# BQ25895_BMS_Module.net
KiCad netlist of a schematic drawn in Altium Designer
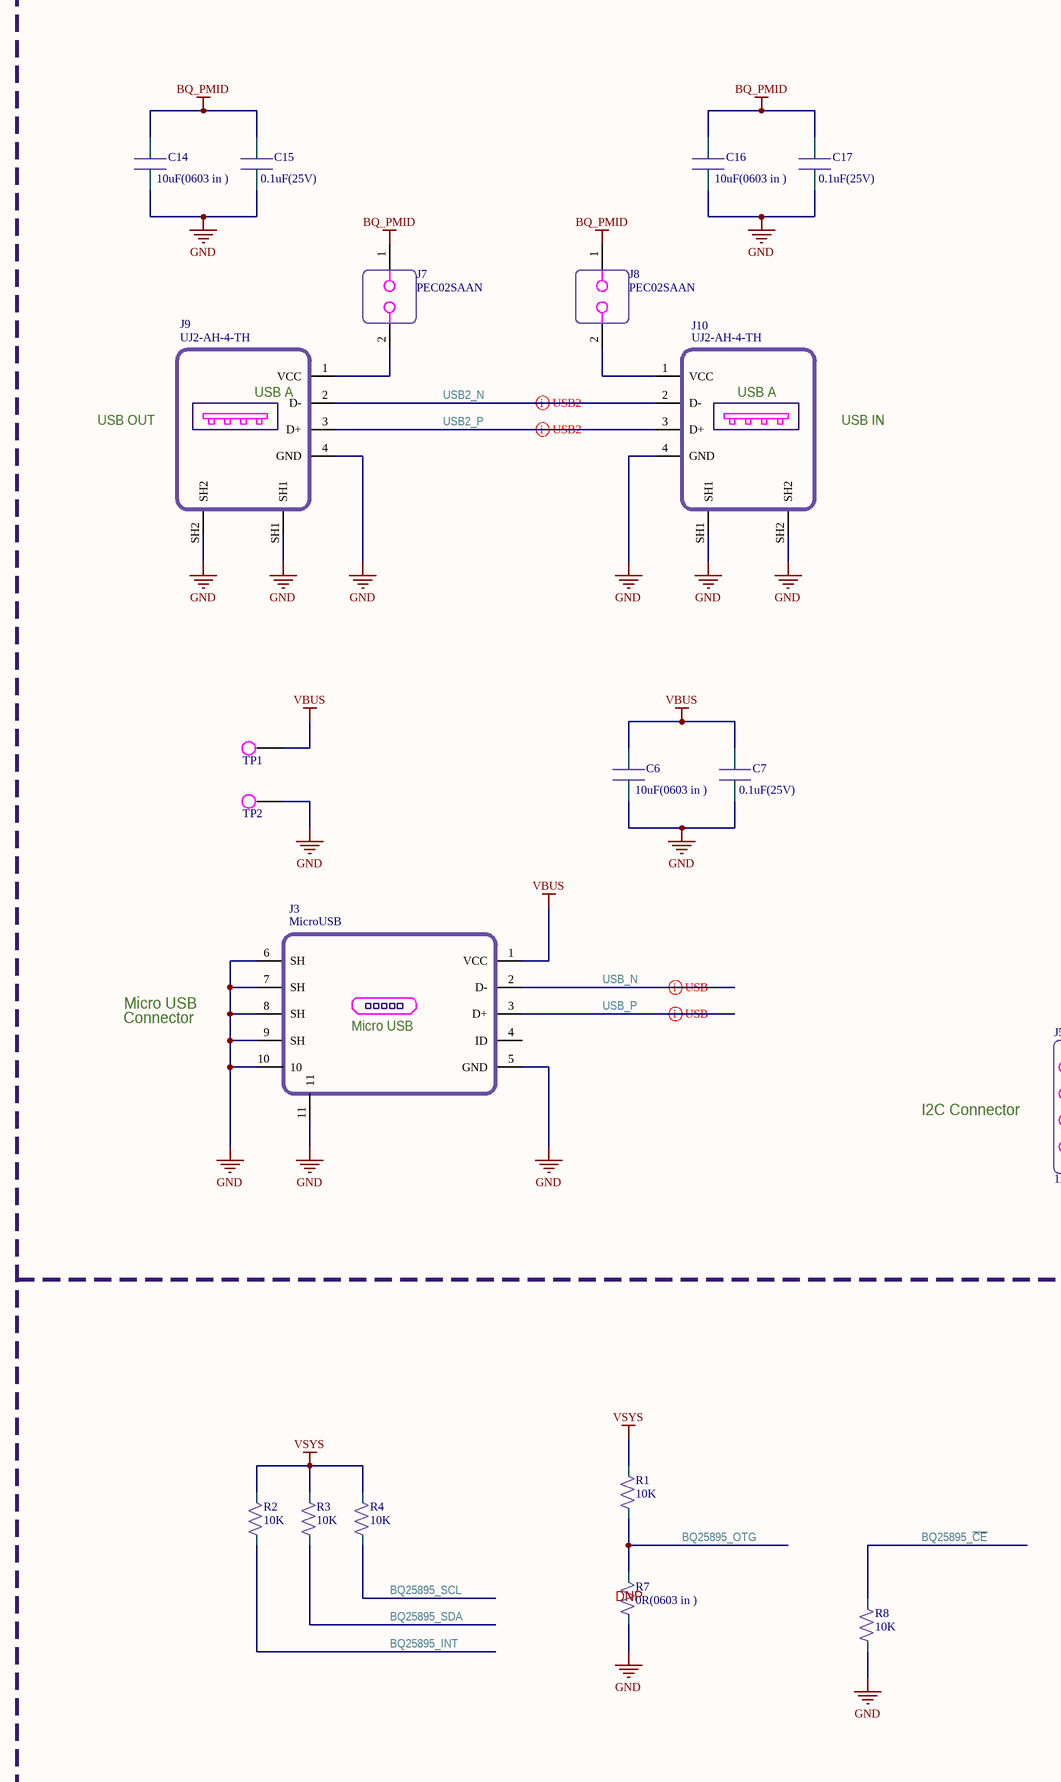
[diagram p0: BQ25895_BMS_Module.SchDoc, left]
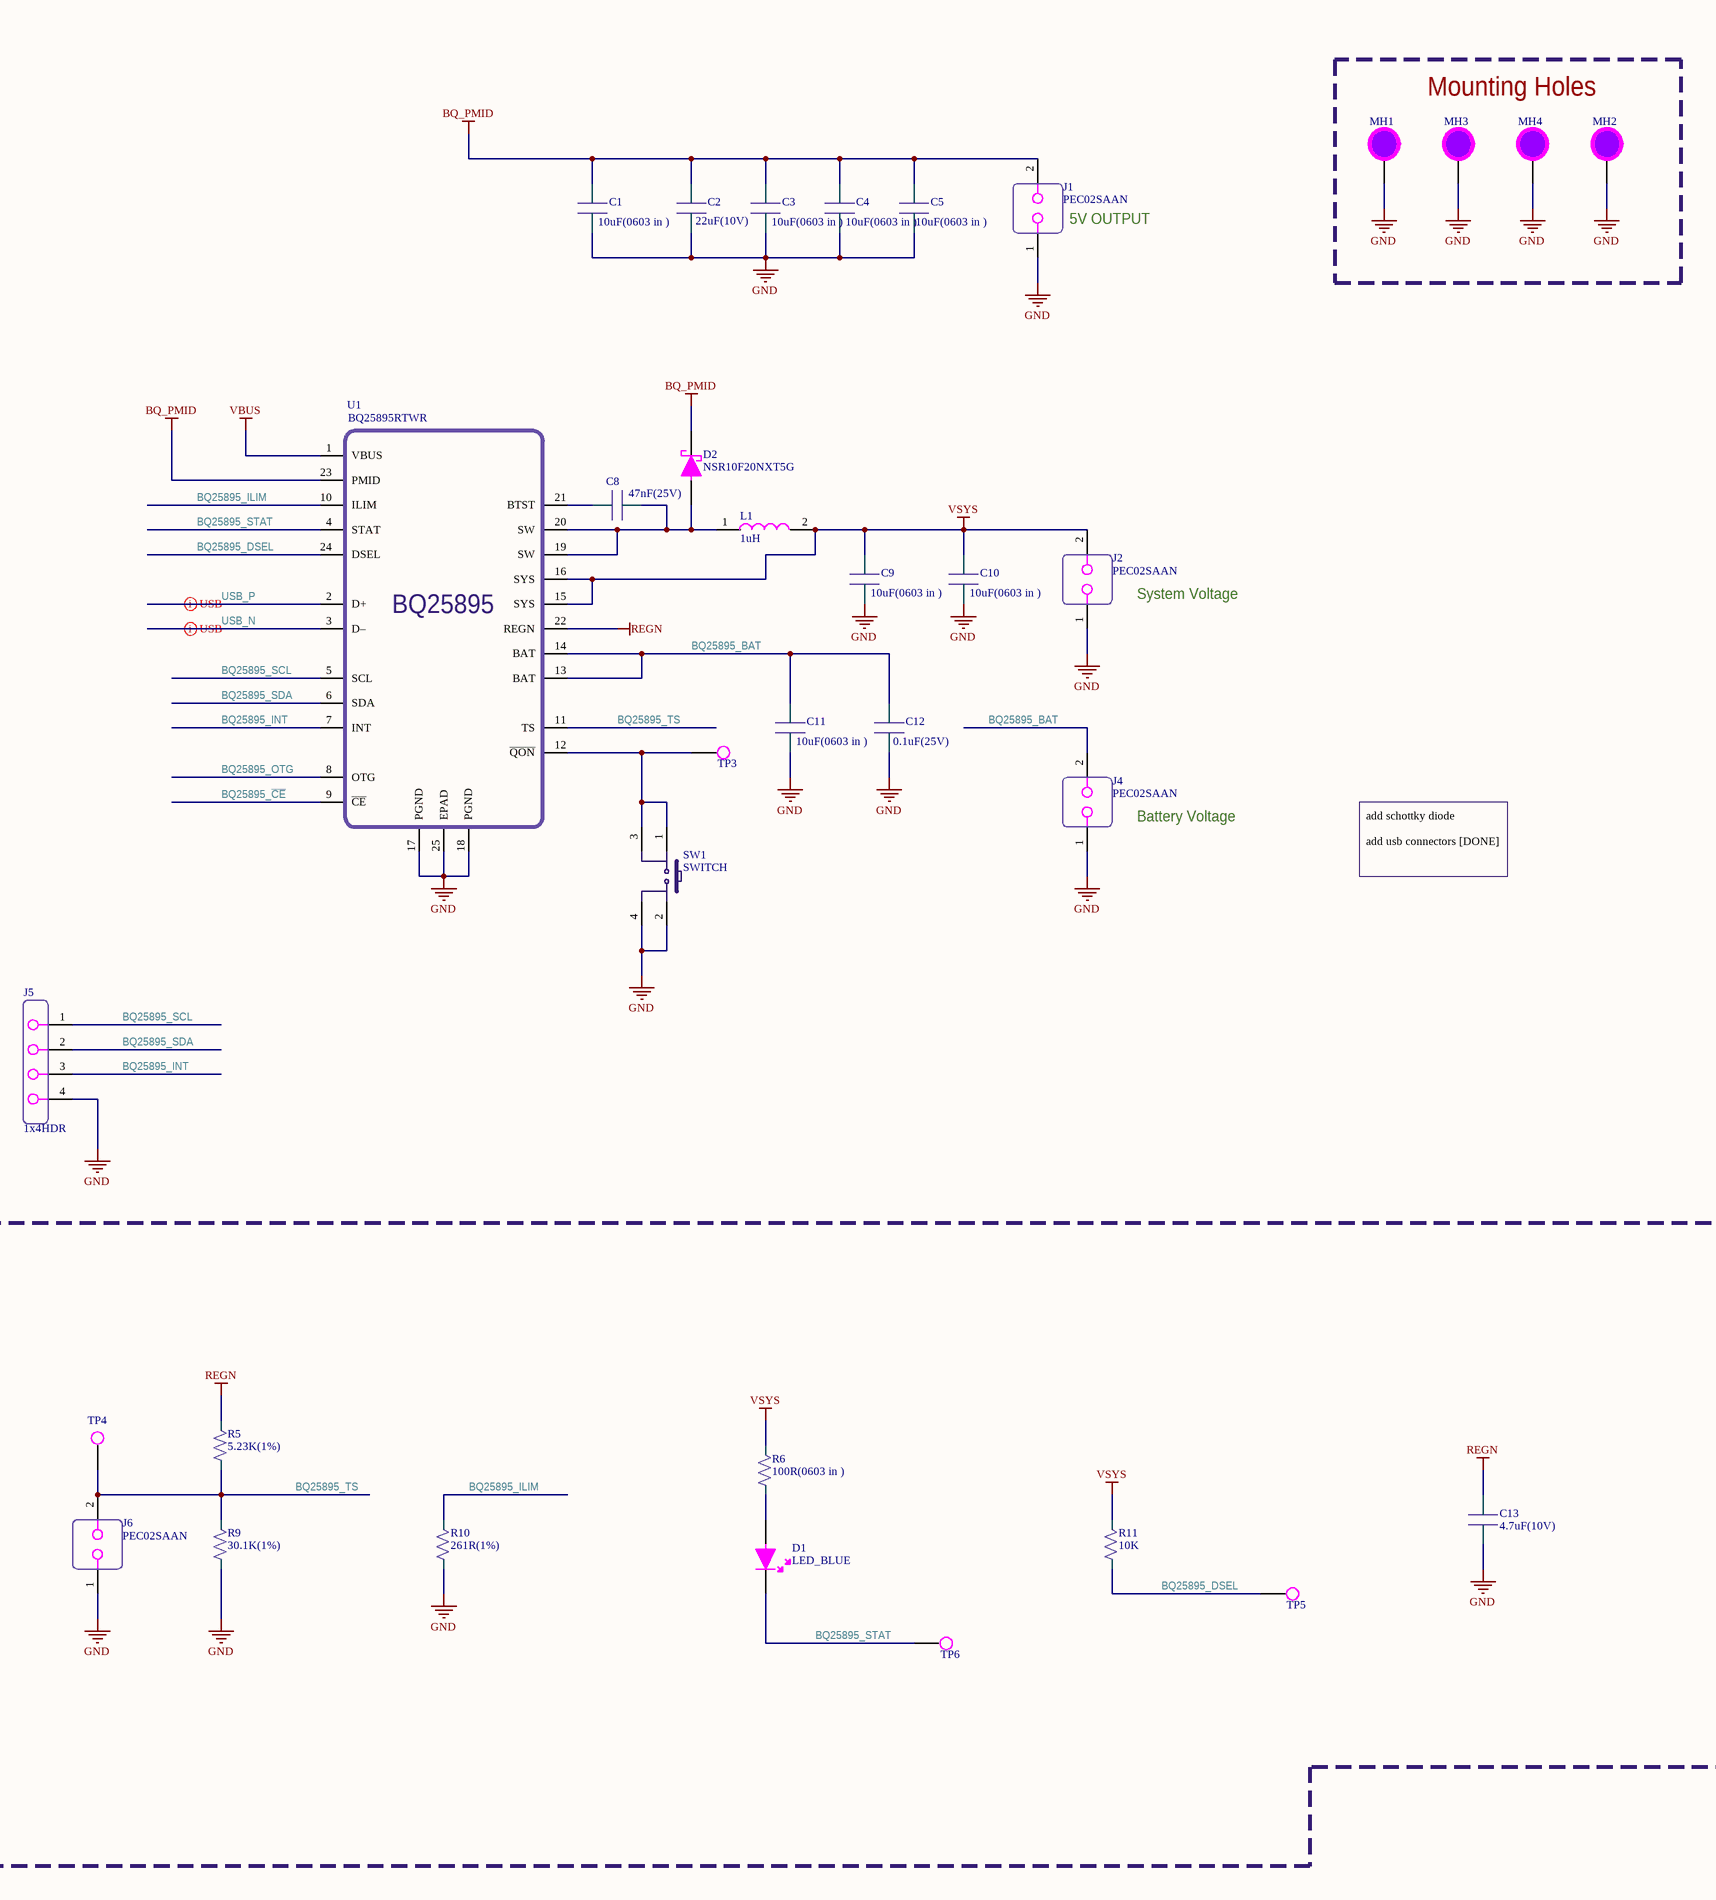
[diagram p1: BQ25895_BMS_Module.SchDoc, right]

(export (version "E")
  (design (tool "Eeschema 10.0.6"))
  (components
    (comp (ref "C1")
      (value "10uF(0603 in )")
      (footprint "Capacitor_0603")
      (description "10µF ±10% 25V Ceramic Capacitor X5R 0603 (1608 Metric)")
      (fields
        (field (name "MANUFACTURERPARTNUMBER") "GRM188R61E106KA73D")
        (field (name "MANUFACTURER") "Murata Electronics")
      )
      (libsource (lib "Capacitors") (part "GRM188R61E106KA73D"))
    )
    (comp (ref "C2")
      (value "22uF(10V)")
      (footprint "Capacitor_0805")
      (description "22 µF ±10% 10V Ceramic Capacitor X5R 0805 (2012 Metric)")
      (fields
        (field (name "MANUFACTURERPARTNUMBER") "CL21A226KPCLRNC")
        (field (name "MANUFACTURER") "Samsung Electro-Mechanics")
      )
      (libsource (lib "Capacitors") (part "CL21A226KPCLRNC"))
    )
    (comp (ref "C3")
      (value "10uF(0603 in )")
      (footprint "Capacitor_0603")
      (description "10µF ±10% 25V Ceramic Capacitor X5R 0603 (1608 Metric)")
      (fields
        (field (name "MANUFACTURERPARTNUMBER") "GRM188R61E106KA73D")
        (field (name "MANUFACTURER") "Murata Electronics")
      )
      (libsource (lib "Capacitors") (part "GRM188R61E106KA73D"))
    )
    (comp (ref "C4")
      (value "10uF(0603 in )")
      (footprint "Capacitor_0603")
      (description "10µF ±10% 25V Ceramic Capacitor X5R 0603 (1608 Metric)")
      (fields
        (field (name "MANUFACTURERPARTNUMBER") "GRM188R61E106KA73D")
        (field (name "MANUFACTURER") "Murata Electronics")
      )
      (libsource (lib "Capacitors") (part "GRM188R61E106KA73D"))
    )
    (comp (ref "C5")
      (value "10uF(0603 in )")
      (footprint "Capacitor_0603")
      (description "10µF ±10% 25V Ceramic Capacitor X5R 0603 (1608 Metric)")
      (fields
        (field (name "MANUFACTURERPARTNUMBER") "GRM188R61E106KA73D")
        (field (name "MANUFACTURER") "Murata Electronics")
      )
      (libsource (lib "Capacitors") (part "GRM188R61E106KA73D"))
    )
    (comp (ref "C6")
      (value "10uF(0603 in )")
      (footprint "Capacitor_0603")
      (description "10µF ±10% 25V Ceramic Capacitor X5R 0603 (1608 Metric)")
      (fields
        (field (name "MANUFACTURERPARTNUMBER") "GRM188R61E106KA73D")
        (field (name "MANUFACTURER") "Murata Electronics")
      )
      (libsource (lib "Capacitors") (part "GRM188R61E106KA73D"))
    )
    (comp (ref "C7")
      (value "0.1uF(25V)")
      (footprint "Capacitor_0603")
      (description "±5% 25V Ceramic Capacitor X7R 0603 (1608 Metric)")
      (fields
        (field (name "MANUFACTURERPARTNUMBER") "C0603C104J3RAC7411")
        (field (name "MANUFACTURER") "KEMET")
      )
      (libsource (lib "Capacitors") (part "C0603C104J3RAC7411"))
    )
    (comp (ref "C8")
      (value "47nF(25V)")
      (footprint "Capacitor_0603")
      (description "0.047 µF ±5% 25V Ceramic Capacitor X7R 0603 (1608 Metric)")
      (fields
        (field (name "MANUFACTURERPARTNUMBER") "C0603C473J3RACAUTO")
        (field (name "MANUFACTURER") "KEMET")
      )
      (libsource (lib "Capacitors") (part "C0603C473J3RACAUTO"))
    )
    (comp (ref "C9")
      (value "10uF(0603 in )")
      (footprint "Capacitor_0603")
      (description "10µF ±10% 25V Ceramic Capacitor X5R 0603 (1608 Metric)")
      (fields
        (field (name "MANUFACTURERPARTNUMBER") "GRM188R61E106KA73D")
        (field (name "MANUFACTURER") "Murata Electronics")
      )
      (libsource (lib "Capacitors") (part "GRM188R61E106KA73D"))
    )
    (comp (ref "C10")
      (value "10uF(0603 in )")
      (footprint "Capacitor_0603")
      (description "10µF ±10% 25V Ceramic Capacitor X5R 0603 (1608 Metric)")
      (fields
        (field (name "MANUFACTURERPARTNUMBER") "GRM188R61E106KA73D")
        (field (name "MANUFACTURER") "Murata Electronics")
      )
      (libsource (lib "Capacitors") (part "GRM188R61E106KA73D"))
    )
    (comp (ref "C11")
      (value "10uF(0603 in )")
      (footprint "Capacitor_0603")
      (description "10µF ±10% 25V Ceramic Capacitor X5R 0603 (1608 Metric)")
      (fields
        (field (name "MANUFACTURERPARTNUMBER") "GRM188R61E106KA73D")
        (field (name "MANUFACTURER") "Murata Electronics")
      )
      (libsource (lib "Capacitors") (part "GRM188R61E106KA73D"))
    )
    (comp (ref "C12")
      (value "0.1uF(25V)")
      (footprint "Capacitor_0603")
      (description "±5% 25V Ceramic Capacitor X7R 0603 (1608 Metric)")
      (fields
        (field (name "MANUFACTURERPARTNUMBER") "C0603C104J3RAC7411")
        (field (name "MANUFACTURER") "KEMET")
      )
      (libsource (lib "Capacitors") (part "C0603C104J3RAC7411"))
    )
    (comp (ref "C13")
      (value "4.7uF(10V)")
      (footprint "Capacitor_0603")
      (description "4.7 µF ±10% 10V Ceramic Capacitor X5R 0603 (1608 Metric)")
      (fields
        (field (name "MANUFACTURERPARTNUMBER") "0603ZD475KAT2A")
        (field (name "MANUFACTURER") "KYOCERA AVX")
      )
      (libsource (lib "Capacitors") (part "0603ZD475KAT2A"))
    )
    (comp (ref "C14")
      (value "10uF(0603 in )")
      (footprint "Capacitor_0603")
      (description "10µF ±10% 25V Ceramic Capacitor X5R 0603 (1608 Metric)")
      (fields
        (field (name "MANUFACTURERPARTNUMBER") "GRM188R61E106KA73D")
        (field (name "MANUFACTURER") "Murata Electronics")
      )
      (libsource (lib "Capacitors") (part "GRM188R61E106KA73D"))
    )
    (comp (ref "C15")
      (value "0.1uF(25V)")
      (footprint "Capacitor_0603")
      (description "±5% 25V Ceramic Capacitor X7R 0603 (1608 Metric)")
      (fields
        (field (name "MANUFACTURERPARTNUMBER") "C0603C104J3RAC7411")
        (field (name "MANUFACTURER") "KEMET")
      )
      (libsource (lib "Capacitors") (part "C0603C104J3RAC7411"))
    )
    (comp (ref "C16")
      (value "10uF(0603 in )")
      (footprint "Capacitor_0603")
      (description "10µF ±10% 25V Ceramic Capacitor X5R 0603 (1608 Metric)")
      (fields
        (field (name "MANUFACTURERPARTNUMBER") "GRM188R61E106KA73D")
        (field (name "MANUFACTURER") "Murata Electronics")
      )
      (libsource (lib "Capacitors") (part "GRM188R61E106KA73D"))
    )
    (comp (ref "C17")
      (value "0.1uF(25V)")
      (footprint "Capacitor_0603")
      (description "±5% 25V Ceramic Capacitor X7R 0603 (1608 Metric)")
      (fields
        (field (name "MANUFACTURERPARTNUMBER") "C0603C104J3RAC7411")
        (field (name "MANUFACTURER") "KEMET")
      )
      (libsource (lib "Capacitors") (part "C0603C104J3RAC7411"))
    )
    (comp (ref "D1")
      (value "LED_BLUE")
      (footprint "0603_LED")
      (description "Blue 465~475nm 0603 Light Emitting Diodes (LED) ROHS")
      (fields
        (field (name "MANUFACTURERPARTNUMBER") "BHC-ZL1M2RY/3T")
        (field (name "MANUFACTURER") "Everlight Elec")
      )
      (libsource (lib "Diodes") (part "BHC-ZL1M2RY/3T"))
    )
    (comp (ref "D2")
      (value "NSR10F20NXT5G")
      (footprint "NSR10F20NXT5G")
      (description "Diode Schottky 20 V 1A (DC) Surface Mount 2-DSN (1.4x0.6)")
      (fields (field (name "MANUFACTURER") "ON Semiconductor"))
      (libsource (lib "Diodes") (part "NSR10F20NXT5G"))
    )
    (comp (ref "J1")
      (value "PEC02SAAN")
      (footprint "P2.541X2HDR")
      (description "Connector Header Through Hole 2 position 0.100\" (2.54mm)")
      (libsource (lib "connectors") (part "PEC02SAAN"))
    )
    (comp (ref "J2")
      (value "PEC02SAAN")
      (footprint "P2.541X2HDR")
      (description "Connector Header Through Hole 2 position 0.100\" (2.54mm)")
      (libsource (lib "connectors") (part "PEC02SAAN"))
    )
    (comp (ref "J3")
      (value "MicroUSB")
      (footprint "Micro USB")
      (description "USB - micro B USB 2.0 Receptacle Connector 5 Position Surface Mount, Right Angle; Through Hole")
      (fields
        (field (name "MANUFACTURERPARTNUMBER") "629105150521")
        (field (name "MANUFACTURER") "Würth Elektronik")
      )
      (libsource (lib "connectors") (part "629105150521"))
    )
    (comp (ref "J4")
      (value "PEC02SAAN")
      (footprint "P2.541X2HDR")
      (description "Connector Header Through Hole 2 position 0.100\" (2.54mm)")
      (libsource (lib "connectors") (part "PEC02SAAN"))
    )
    (comp (ref "J5")
      (value "1x4HDR")
      (footprint "P2.541X4HDR")
      (description "Connector Header Through Hole 4 position 0.100\" (2.54mm)")
      (fields (field (name "MANUFACTURERPARTNUMBER") "PEC04SAAN"))
      (libsource (lib "connectors") (part "PEC04SAAN"))
    )
    (comp (ref "J6")
      (value "PEC02SAAN")
      (footprint "P2.541X2HDR")
      (description "Connector Header Through Hole 2 position 0.100\" (2.54mm)")
      (libsource (lib "connectors") (part "PEC02SAAN"))
    )
    (comp (ref "J7")
      (value "PEC02SAAN")
      (footprint "P2.541X2HDR")
      (description "Connector Header Through Hole 2 position 0.100\" (2.54mm)")
      (libsource (lib "connectors") (part "PEC02SAAN"))
    )
    (comp (ref "J8")
      (value "PEC02SAAN")
      (footprint "P2.541X2HDR")
      (description "Connector Header Through Hole 2 position 0.100\" (2.54mm)")
      (libsource (lib "connectors") (part "PEC02SAAN"))
    )
    (comp (ref "J9")
      (value "UJ2-AH-4-TH")
      (footprint "CUI_UJ2-AH-4-TH")
      (description "USB-A (USB TYPE-A) USB 2.0 Receptacle Connector 4 Position Through Hole, Right Angle")
      (fields (field (name "MANUFACTURER") "CUI Devices"))
      (libsource (lib "connectors") (part "UJ2-AH-4-TH"))
    )
    (comp (ref "J10")
      (value "UJ2-AH-4-TH")
      (footprint "CUI_UJ2-AH-4-TH")
      (description "USB-A (USB TYPE-A) USB 2.0 Receptacle Connector 4 Position Through Hole, Right Angle")
      (fields (field (name "MANUFACTURER") "CUI Devices"))
      (libsource (lib "connectors") (part "UJ2-AH-4-TH"))
    )
    (comp (ref "L1")
      (value "1uH")
      (footprint "VLS6045EX-1R0N")
      (description "FIXED IND 1UH 6A 16 MOHM SMD")
      (fields
        (field (name "MANUFACTURERPARTNUMBER") "VLS6045EX-1R0N")
        (field (name "MANUFACTURER") "TDK Corporation")
      )
      (libsource (lib "Inductors and Coils") (part "VLS6045EX-1R0N"))
    )
    (comp (ref "MH1")
      (value "Mounting Hole")
      (footprint "Mounting_Hole_3.3mm")
      (description "3.3mm Mounting Hole")
      (libsource (lib "connectors") (part "3MM_MOUNTING_HOLE"))
    )
    (comp (ref "MH2")
      (value "Mounting Hole")
      (footprint "Mounting_Hole_3.3mm")
      (description "3.3mm Mounting Hole")
      (libsource (lib "connectors") (part "3MM_MOUNTING_HOLE"))
    )
    (comp (ref "MH3")
      (value "Mounting Hole")
      (footprint "Mounting_Hole_3.3mm")
      (description "3.3mm Mounting Hole")
      (libsource (lib "connectors") (part "3MM_MOUNTING_HOLE"))
    )
    (comp (ref "MH4")
      (value "Mounting Hole")
      (footprint "Mounting_Hole_3.3mm")
      (description "3.3mm Mounting Hole")
      (libsource (lib "connectors") (part "3MM_MOUNTING_HOLE"))
    )
    (comp (ref "R1")
      (value "10K")
      (footprint "RESISTOR0603")
      (description "10 kOhms ±5% 0.1W, 1/10W Chip Resistor 0603 (1608 Metric) Automotive AEC-Q200 Thick Film")
      (fields
        (field (name "MANUFACTURERPARTNUMBER") "RMCF0603JT10K0")
        (field (name "MANUFACTURER") "Stackpole Electronics Inc")
      )
      (libsource (lib "Resistors") (part "RMCF0603JT10K0"))
    )
    (comp (ref "R2")
      (value "10K")
      (footprint "RESISTOR0603")
      (description "10 kOhms ±5% 0.1W, 1/10W Chip Resistor 0603 (1608 Metric) Automotive AEC-Q200 Thick Film")
      (fields
        (field (name "MANUFACTURERPARTNUMBER") "RMCF0603JT10K0")
        (field (name "MANUFACTURER") "Stackpole Electronics Inc")
      )
      (libsource (lib "Resistors") (part "RMCF0603JT10K0"))
    )
    (comp (ref "R3")
      (value "10K")
      (footprint "RESISTOR0603")
      (description "10 kOhms ±5% 0.1W, 1/10W Chip Resistor 0603 (1608 Metric) Automotive AEC-Q200 Thick Film")
      (fields
        (field (name "MANUFACTURERPARTNUMBER") "RMCF0603JT10K0")
        (field (name "MANUFACTURER") "Stackpole Electronics Inc")
      )
      (libsource (lib "Resistors") (part "RMCF0603JT10K0"))
    )
    (comp (ref "R4")
      (value "10K")
      (footprint "RESISTOR0603")
      (description "10 kOhms ±5% 0.1W, 1/10W Chip Resistor 0603 (1608 Metric) Automotive AEC-Q200 Thick Film")
      (fields
        (field (name "MANUFACTURERPARTNUMBER") "RMCF0603JT10K0")
        (field (name "MANUFACTURER") "Stackpole Electronics Inc")
      )
      (libsource (lib "Resistors") (part "RMCF0603JT10K0"))
    )
    (comp (ref "R5")
      (value "5.23K(1%)")
      (footprint "RESISTOR0603")
      (description "5.23 kOhms ±1% 0.1W, 1/10W Chip Resistor 0603 (1608 Metric) Automotive AEC-Q200 Thick Film")
      (fields
        (field (name "MANUFACTURERPARTNUMBER") "RMCF0603FT5K23")
        (field (name "MANUFACTURER") "Stackpole Electronics Inc")
      )
      (libsource (lib "Resistors") (part "RMCF0603FT5K23"))
    )
    (comp (ref "R6")
      (value "100R(0603 in )")
      (footprint "RESISTOR0603")
      (description "100 Ohms ±5% 0.1W, 1/10W Chip Resistor 0603 (1608 Metric)  Thick Film")
      (fields (field (name "MANUFACTURER PART NUMBER") "CRCW0603100RJNEAC"))
      (libsource (lib "Resistors") (part "CRCW0603100RJNEAC"))
    )
    (comp (ref "R7")
      (value "0R(0603 in )")
      (footprint "RESISTOR0603")
      (description "0 Ohms ±5% 0.063W, 1/16W Chip Resistor 0603 (1608 Metric)  Thick Film")
      (fields (field (name "MANUFACTURER PART NUMBER") "SR1-0603-000"))
      (libsource (lib "Resistors") (part "SR1-0603-000"))
    )
    (comp (ref "R8")
      (value "10K")
      (footprint "RESISTOR0603")
      (description "10 kOhms ±5% 0.1W, 1/10W Chip Resistor 0603 (1608 Metric) Automotive AEC-Q200 Thick Film")
      (fields
        (field (name "MANUFACTURERPARTNUMBER") "RMCF0603JT10K0")
        (field (name "MANUFACTURER") "Stackpole Electronics Inc")
      )
      (libsource (lib "Resistors") (part "RMCF0603JT10K0"))
    )
    (comp (ref "R9")
      (value "30.1K(1%)")
      (footprint "RESISTOR0603")
      (description "30.1 kOhms ±1% 0.1W, 1/10W Chip Resistor 0603 (1608 Metric) Automotive AEC-Q200 Thick Film")
      (fields
        (field (name "MANUFACTURERPARTNUMBER") "RMCF0603FG30K1")
        (field (name "MANUFACTURER") "Stackpole Electronics Inc")
      )
      (libsource (lib "Resistors") (part "RMCF0603FG30K1"))
    )
    (comp (ref "R10")
      (value "261R(1%)")
      (footprint "RESISTOR0603")
      (description "Thick Film Resistors 0603 261ohm 1% Anti-Surge AEC-Q200")
      (fields
        (field (name "MANUFACTURERPARTNUMBER") "ERJ-PA3F2610V")
        (field (name "MANUFACTURER") "Panasonic")
      )
      (libsource (lib "Resistors") (part "ERJ-PA3F2610V"))
    )
    (comp (ref "R11")
      (value "10K")
      (footprint "RESISTOR0603")
      (description "10 kOhms ±5% 0.1W, 1/10W Chip Resistor 0603 (1608 Metric) Automotive AEC-Q200 Thick Film")
      (fields
        (field (name "MANUFACTURERPARTNUMBER") "RMCF0603JT10K0")
        (field (name "MANUFACTURER") "Stackpole Electronics Inc")
      )
      (libsource (lib "Resistors") (part "RMCF0603JT10K0"))
    )
    (comp (ref "SW1")
      (value "SWITCH")
      (footprint "PushButton nf")
      (description "Tactile Switch SPST-NO Top Actuated Surface Mount")
      (fields (field (name "MANUFACTURERPARTNUMBER") "TL1105DF160Q") (field (name "MANUFACTURER") "E-Switch"))
      (libsource (lib "Connectors") (part "TL1105DF160Q"))
    )
    (comp (ref "TP1")
      (value "Test Pad")
      (footprint "TestPoint")
      (description "2mm Diameter test point")
      (libsource (lib "connectors") (part "TestPoint"))
    )
    (comp (ref "TP2")
      (value "Test Pad")
      (footprint "TestPoint")
      (description "2mm Diameter test point")
      (libsource (lib "connectors") (part "TestPoint"))
    )
    (comp (ref "TP3")
      (value "Test Pad")
      (footprint "TestPoint")
      (description "2mm Diameter test point")
      (libsource (lib "connectors") (part "TestPoint"))
    )
    (comp (ref "TP4")
      (value "Test Pad")
      (footprint "TestPoint")
      (description "2mm Diameter test point")
      (libsource (lib "connectors") (part "TestPoint"))
    )
    (comp (ref "TP5")
      (value "Test Pad")
      (footprint "TestPoint")
      (description "2mm Diameter test point")
      (libsource (lib "connectors") (part "TestPoint"))
    )
    (comp (ref "TP6")
      (value "Test Pad")
      (footprint "TestPoint")
      (description "2mm Diameter test point")
      (libsource (lib "connectors") (part "TestPoint"))
    )
    (comp (ref "U1")
      (value "BQ25895RTWR")
      (footprint "24-WQFN")
      (description "Charger IC Lithium Ion/Polymer 24-WQFN (4x4)")
      (fields (field (name "MANUFACTURER") "Texas Instruments"))
      (libsource (lib "integrated_circuits") (part "BQ25895RTWR"))
    )
  )
  (nets
    (net (code "1") (name "/BQ25895_BAT") (class "Default")
      (node (ref "C11") (pin "2") (pinfunction "2_2") (pintype "passive"))
      (node (ref "C12") (pin "2") (pinfunction "2_2") (pintype "passive"))
      (node (ref "J4") (pin "2") (pinfunction "2_2") (pintype "passive"))
      (node (ref "U1") (pin "13") (pinfunction "BAT_13") (pintype "passive"))
      (node (ref "U1") (pin "14") (pinfunction "BAT_14") (pintype "passive"))
    )
    (net (code "2") (name "/BQ25895_DSEL") (class "Default")
      (node (ref "R11") (pin "1") (pinfunction "1_1") (pintype "passive"))
      (node (ref "TP5") (pin "1") (pinfunction "1_1") (pintype "passive"))
      (node (ref "U1") (pin "24") (pinfunction "DSEL_24") (pintype "passive"))
    )
    (net (code "3") (name "/BQ25895_ILIM") (class "Default")
      (node (ref "R10") (pin "2") (pinfunction "2_2") (pintype "passive"))
      (node (ref "U1") (pin "10") (pinfunction "ILIM_10") (pintype "passive"))
    )
    (net (code "4") (name "/BQ25895_INT") (class "Default")
      (node (ref "J5") (pin "3") (pinfunction "3_3") (pintype "passive"))
      (node (ref "R2") (pin "1") (pinfunction "1_1") (pintype "passive"))
      (node (ref "U1") (pin "7") (pinfunction "INT_7") (pintype "passive"))
    )
    (net (code "5") (name "/BQ25895_OTG") (class "Default")
      (node (ref "R1") (pin "1") (pinfunction "1_1") (pintype "passive"))
      (node (ref "R7") (pin "2") (pinfunction "2_2") (pintype "passive"))
      (node (ref "U1") (pin "8") (pinfunction "OTG_8") (pintype "passive"))
    )
    (net (code "6") (name "/BQ25895_SCL") (class "Default")
      (node (ref "J5") (pin "1") (pinfunction "1_1") (pintype "passive"))
      (node (ref "R4") (pin "1") (pinfunction "1_1") (pintype "passive"))
      (node (ref "U1") (pin "5") (pinfunction "SCL_5") (pintype "passive"))
    )
    (net (code "7") (name "/BQ25895_SDA") (class "Default")
      (node (ref "J5") (pin "2") (pinfunction "2_2") (pintype "passive"))
      (node (ref "R3") (pin "1") (pinfunction "1_1") (pintype "passive"))
      (node (ref "U1") (pin "6") (pinfunction "SDA_6") (pintype "passive"))
    )
    (net (code "8") (name "/BQ25895_STAT") (class "Default")
      (node (ref "D1") (pin "2") (pinfunction "2_2") (pintype "passive"))
      (node (ref "TP6") (pin "1") (pinfunction "1_1") (pintype "passive"))
      (node (ref "U1") (pin "4") (pinfunction "STAT_4") (pintype "passive"))
    )
    (net (code "9") (name "/BQ25895_TS") (class "Default")
      (node (ref "J6") (pin "2") (pinfunction "2_2") (pintype "passive"))
      (node (ref "R5") (pin "1") (pinfunction "1_1") (pintype "passive"))
      (node (ref "R9") (pin "2") (pinfunction "2_2") (pintype "passive"))
      (node (ref "TP4") (pin "1") (pinfunction "1_1") (pintype "passive"))
      (node (ref "U1") (pin "11") (pinfunction "TS_11") (pintype "passive"))
    )
    (net (code "10") (name "/BQ25895_~{CE}") (class "Default")
      (node (ref "R8") (pin "2") (pinfunction "2_2") (pintype "passive"))
      (node (ref "U1") (pin "9") (pinfunction "~{CE}_9") (pintype "passive"))
    )
    (net (code "11") (name "/USB2_N") (class "Default")
      (node (ref "J10") (pin "2") (pinfunction "D-_2") (pintype "passive"))
      (node (ref "J9") (pin "2") (pinfunction "D-_2") (pintype "passive"))
    )
    (net (code "12") (name "/USB2_P") (class "Default")
      (node (ref "J10") (pin "3") (pinfunction "D+_3") (pintype "passive"))
      (node (ref "J9") (pin "3") (pinfunction "D+_3") (pintype "passive"))
    )
    (net (code "13") (name "/USB_N") (class "Default")
      (node (ref "J3") (pin "2") (pinfunction "D-_2") (pintype "passive"))
      (node (ref "U1") (pin "3") (pinfunction "D–_3") (pintype "passive"))
    )
    (net (code "14") (name "/USB_P") (class "Default")
      (node (ref "J3") (pin "3") (pinfunction "D+_3") (pintype "passive"))
      (node (ref "U1") (pin "2") (pinfunction "D+_2") (pintype "passive"))
    )
    (net (code "15") (name "BQ_PMID") (class "Default")
      (node (ref "C1") (pin "2") (pinfunction "2_2") (pintype "passive"))
      (node (ref "C14") (pin "2") (pinfunction "2_2") (pintype "passive"))
      (node (ref "C15") (pin "2") (pinfunction "2_2") (pintype "passive"))
      (node (ref "C16") (pin "2") (pinfunction "2_2") (pintype "passive"))
      (node (ref "C17") (pin "2") (pinfunction "2_2") (pintype "passive"))
      (node (ref "C2") (pin "2") (pinfunction "2_2") (pintype "passive"))
      (node (ref "C3") (pin "2") (pinfunction "2_2") (pintype "passive"))
      (node (ref "C4") (pin "2") (pinfunction "2_2") (pintype "passive"))
      (node (ref "C5") (pin "2") (pinfunction "2_2") (pintype "passive"))
      (node (ref "D2") (pin "1") (pinfunction "1_1") (pintype "passive"))
      (node (ref "J1") (pin "2") (pinfunction "2_2") (pintype "passive"))
      (node (ref "J7") (pin "1") (pinfunction "1_1") (pintype "passive"))
      (node (ref "J8") (pin "1") (pinfunction "1_1") (pintype "passive"))
      (node (ref "U1") (pin "23") (pinfunction "PMID_23") (pintype "passive"))
    )
    (net (code "16") (name "GND") (class "Default")
      (node (ref "C1") (pin "1") (pinfunction "1_1") (pintype "passive"))
      (node (ref "C10") (pin "1") (pinfunction "1_1") (pintype "passive"))
      (node (ref "C11") (pin "1") (pinfunction "1_1") (pintype "passive"))
      (node (ref "C12") (pin "1") (pinfunction "1_1") (pintype "passive"))
      (node (ref "C13") (pin "1") (pinfunction "1_1") (pintype "passive"))
      (node (ref "C14") (pin "1") (pinfunction "1_1") (pintype "passive"))
      (node (ref "C15") (pin "1") (pinfunction "1_1") (pintype "passive"))
      (node (ref "C16") (pin "1") (pinfunction "1_1") (pintype "passive"))
      (node (ref "C17") (pin "1") (pinfunction "1_1") (pintype "passive"))
      (node (ref "C2") (pin "1") (pinfunction "1_1") (pintype "passive"))
      (node (ref "C3") (pin "1") (pinfunction "1_1") (pintype "passive"))
      (node (ref "C4") (pin "1") (pinfunction "1_1") (pintype "passive"))
      (node (ref "C5") (pin "1") (pinfunction "1_1") (pintype "passive"))
      (node (ref "C6") (pin "1") (pinfunction "1_1") (pintype "passive"))
      (node (ref "C7") (pin "1") (pinfunction "1_1") (pintype "passive"))
      (node (ref "C9") (pin "1") (pinfunction "1_1") (pintype "passive"))
      (node (ref "J1") (pin "1") (pinfunction "1_1") (pintype "passive"))
      (node (ref "J10") (pin "4") (pinfunction "GND_4") (pintype "passive"))
      (node (ref "J10") (pin "SH1") (pinfunction "SH1_SH1") (pintype "passive"))
      (node (ref "J10") (pin "SH2") (pinfunction "SH2_SH2") (pintype "passive"))
      (node (ref "J2") (pin "1") (pinfunction "1_1") (pintype "passive"))
      (node (ref "J3") (pin "10") (pinfunction "10_10") (pintype "passive"))
      (node (ref "J3") (pin "11") (pinfunction "11_11") (pintype "passive"))
      (node (ref "J3") (pin "5") (pinfunction "GND_5") (pintype "passive"))
      (node (ref "J3") (pin "6") (pinfunction "SH_6") (pintype "passive"))
      (node (ref "J3") (pin "7") (pinfunction "SH_7") (pintype "passive"))
      (node (ref "J3") (pin "8") (pinfunction "SH_8") (pintype "passive"))
      (node (ref "J3") (pin "9") (pinfunction "SH_9") (pintype "passive"))
      (node (ref "J4") (pin "1") (pinfunction "1_1") (pintype "passive"))
      (node (ref "J5") (pin "4") (pinfunction "4_4") (pintype "passive"))
      (node (ref "J6") (pin "1") (pinfunction "1_1") (pintype "passive"))
      (node (ref "J9") (pin "4") (pinfunction "GND_4") (pintype "passive"))
      (node (ref "J9") (pin "SH1") (pinfunction "SH1_SH1") (pintype "passive"))
      (node (ref "J9") (pin "SH2") (pinfunction "SH2_SH2") (pintype "passive"))
      (node (ref "MH1") (pin "1") (pinfunction "1_1") (pintype "passive"))
      (node (ref "MH2") (pin "1") (pinfunction "1_1") (pintype "passive"))
      (node (ref "MH3") (pin "1") (pinfunction "1_1") (pintype "passive"))
      (node (ref "MH4") (pin "1") (pinfunction "1_1") (pintype "passive"))
      (node (ref "R10") (pin "1") (pinfunction "1_1") (pintype "passive"))
      (node (ref "R7") (pin "1") (pinfunction "1_1") (pintype "passive"))
      (node (ref "R8") (pin "1") (pinfunction "1_1") (pintype "passive"))
      (node (ref "R9") (pin "1") (pinfunction "1_1") (pintype "passive"))
      (node (ref "SW1") (pin "2") (pinfunction "2_2") (pintype "passive"))
      (node (ref "SW1") (pin "4") (pinfunction "4_4") (pintype "passive"))
      (node (ref "TP2") (pin "1") (pinfunction "1_1") (pintype "passive"))
      (node (ref "U1") (pin "17") (pinfunction "PGND_17") (pintype "passive"))
      (node (ref "U1") (pin "18") (pinfunction "PGND_18") (pintype "passive"))
      (node (ref "U1") (pin "25") (pinfunction "EPAD_25") (pintype "passive"))
    )
    (net (code "17") (name "Net-(C8-Pad2)") (class "Default")
      (node (ref "C8") (pin "2") (pinfunction "2_2") (pintype "passive"))
      (node (ref "D2") (pin "2") (pinfunction "2_2") (pintype "passive"))
      (node (ref "L1") (pin "1") (pinfunction "1_1") (pintype "passive"))
      (node (ref "U1") (pin "19") (pinfunction "SW_19") (pintype "passive"))
      (node (ref "U1") (pin "20") (pinfunction "SW_20") (pintype "passive"))
    )
    (net (code "18") (name "Net-(D1-Pad1)") (class "Default")
      (node (ref "D1") (pin "1") (pinfunction "1_1") (pintype "passive"))
      (node (ref "R6") (pin "1") (pinfunction "1_1") (pintype "passive"))
    )
    (net (code "19") (name "Net-(J9-VCC)") (class "Default")
      (node (ref "J7") (pin "2") (pinfunction "2_2") (pintype "passive"))
      (node (ref "J9") (pin "1") (pinfunction "VCC_1") (pintype "passive"))
    )
    (net (code "20") (name "Net-(J10-VCC)") (class "Default")
      (node (ref "J10") (pin "1") (pinfunction "VCC_1") (pintype "passive"))
      (node (ref "J8") (pin "2") (pinfunction "2_2") (pintype "passive"))
    )
    (net (code "21") (name "Net-(U1-BTST)") (class "Default")
      (node (ref "C8") (pin "1") (pinfunction "1_1") (pintype "passive"))
      (node (ref "U1") (pin "21") (pinfunction "BTST_21") (pintype "passive"))
    )
    (net (code "22") (name "Net-(U1-~{QON})") (class "Default")
      (node (ref "SW1") (pin "1") (pinfunction "1_1") (pintype "passive"))
      (node (ref "SW1") (pin "3") (pinfunction "3_3") (pintype "passive"))
      (node (ref "TP3") (pin "1") (pinfunction "1_1") (pintype "passive"))
      (node (ref "U1") (pin "12") (pinfunction "~{QON}_12") (pintype "passive"))
    )
    (net (code "23") (name "REGN") (class "Default")
      (node (ref "C13") (pin "2") (pinfunction "2_2") (pintype "passive"))
      (node (ref "R5") (pin "2") (pinfunction "2_2") (pintype "passive"))
      (node (ref "U1") (pin "22") (pinfunction "REGN_22") (pintype "passive"))
    )
    (net (code "24") (name "VBUS") (class "Default")
      (node (ref "C6") (pin "2") (pinfunction "2_2") (pintype "passive"))
      (node (ref "C7") (pin "2") (pinfunction "2_2") (pintype "passive"))
      (node (ref "J3") (pin "1") (pinfunction "VCC_1") (pintype "passive"))
      (node (ref "TP1") (pin "1") (pinfunction "1_1") (pintype "passive"))
      (node (ref "U1") (pin "1") (pinfunction "VBUS_1") (pintype "passive"))
    )
    (net (code "25") (name "VSYS") (class "Default")
      (node (ref "C10") (pin "2") (pinfunction "2_2") (pintype "passive"))
      (node (ref "C9") (pin "2") (pinfunction "2_2") (pintype "passive"))
      (node (ref "J2") (pin "2") (pinfunction "2_2") (pintype "passive"))
      (node (ref "L1") (pin "2") (pinfunction "2_2") (pintype "passive"))
      (node (ref "R1") (pin "2") (pinfunction "2_2") (pintype "passive"))
      (node (ref "R11") (pin "2") (pinfunction "2_2") (pintype "passive"))
      (node (ref "R2") (pin "2") (pinfunction "2_2") (pintype "passive"))
      (node (ref "R3") (pin "2") (pinfunction "2_2") (pintype "passive"))
      (node (ref "R4") (pin "2") (pinfunction "2_2") (pintype "passive"))
      (node (ref "R6") (pin "2") (pinfunction "2_2") (pintype "passive"))
      (node (ref "U1") (pin "15") (pinfunction "SYS_15") (pintype "passive"))
      (node (ref "U1") (pin "16") (pinfunction "SYS_16") (pintype "passive"))
    )
    (net (code "26") (name "unconnected-(J3-ID-Pad4)") (class "Default")
      (node (ref "J3") (pin "4") (pinfunction "ID_4") (pintype "passive"))
    )
  )
)
